# MyFirstEagleProject.net
KiCad netlist of a schematic drawn in EAGLE
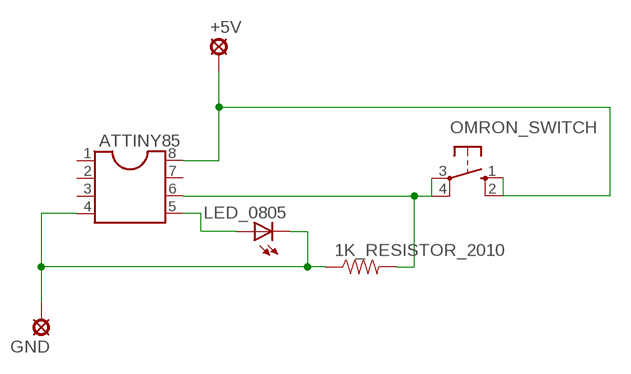
[diagram p0: schematic, sheet 1]

(export (version "E")
  (design (tool "Eeschema 10.0.6"))
  (components
    (comp (ref "+5V")
      (value "SE14")
      (footprint "eagle-import:SE14")
      (libsource (lib "eagle-import") (part "SE14"))
    )
    (comp (ref "1K_RESISTOR_2010")
      (value "RESISTOR2010")
      (footprint "eagle-import:R2010")
      (libsource (lib "eagle-import") (part "RESISTOR2010"))
    )
    (comp (ref "ATTINY85")
      (value "DIL8S")
      (footprint "eagle-import:SOCKET-08")
      (libsource (lib "eagle-import") (part "DIL8S"))
    )
    (comp (ref "GND")
      (value "SE14")
      (footprint "eagle-import:SE14")
      (libsource (lib "eagle-import") (part "SE14"))
    )
    (comp (ref "LED_0805")
      (value "LEDCHIPLED_0805")
      (footprint "eagle-import:CHIPLED_0805")
      (libsource (lib "eagle-import") (part "LEDCHIPLED_0805"))
    )
    (comp (ref "OMRON_SWITCH")
      (value "10-XX")
      (footprint "eagle-import:B3F-10XX")
      (fields (field (name "MPN") "B3F-1000"))
      (libsource (lib "eagle-import") (part "10-XX"))
    )
  )
  (nets
    (net (code "1") (name "Net-(1K_RESISTOR_2010-Pad1)") (class "Default")
      (node (ref "1K_RESISTOR_2010") (pin "1") (pinfunction "1_1") (pintype "passive"))
      (node (ref "ATTINY85") (pin "4") (pinfunction "4_4") (pintype "passive"))
      (node (ref "GND") (pin "MP") (pinfunction "MP_MP") (pintype "passive"))
      (node (ref "LED_0805") (pin "C") (pinfunction "C_C") (pintype "passive"))
    )
    (net (code "2") (name "Net-(ATTINY85-Pad5)") (class "Default")
      (node (ref "ATTINY85") (pin "5") (pinfunction "5_5") (pintype "passive"))
      (node (ref "LED_0805") (pin "A") (pinfunction "A_A") (pintype "passive"))
    )
    (net (code "3") (name "Net-(OMRON_SWITCH-P)") (class "Default")
      (node (ref "1K_RESISTOR_2010") (pin "2") (pinfunction "2_2") (pintype "passive"))
      (node (ref "ATTINY85") (pin "6") (pinfunction "6_6") (pintype "passive"))
      (node (ref "OMRON_SWITCH") (pin "3") (pinfunction "P_3") (pintype "passive"))
      (node (ref "OMRON_SWITCH") (pin "4") (pinfunction "P1_4") (pintype "passive"))
    )
    (net (code "4") (name "Net-(OMRON_SWITCH-S)") (class "Default")
      (node (ref "+5V") (pin "MP") (pinfunction "MP_MP") (pintype "passive"))
      (node (ref "ATTINY85") (pin "8") (pinfunction "8_8") (pintype "passive"))
      (node (ref "OMRON_SWITCH") (pin "1") (pinfunction "S_1") (pintype "passive"))
      (node (ref "OMRON_SWITCH") (pin "2") (pinfunction "S1_2") (pintype "passive"))
    )
    (net (code "5") (name "unconnected-(ATTINY85-Pad1)") (class "Default")
      (node (ref "ATTINY85") (pin "1") (pinfunction "1_1") (pintype "passive"))
    )
    (net (code "6") (name "unconnected-(ATTINY85-Pad2)") (class "Default")
      (node (ref "ATTINY85") (pin "2") (pinfunction "2_2") (pintype "passive"))
    )
    (net (code "7") (name "unconnected-(ATTINY85-Pad3)") (class "Default")
      (node (ref "ATTINY85") (pin "3") (pinfunction "3_3") (pintype "passive"))
    )
    (net (code "8") (name "unconnected-(ATTINY85-Pad7)") (class "Default")
      (node (ref "ATTINY85") (pin "7") (pinfunction "7_7") (pintype "passive"))
    )
  )
)
